# OSO-SCAP-A1-01.net
KiCad netlist of a schematic drawn in EAGLE
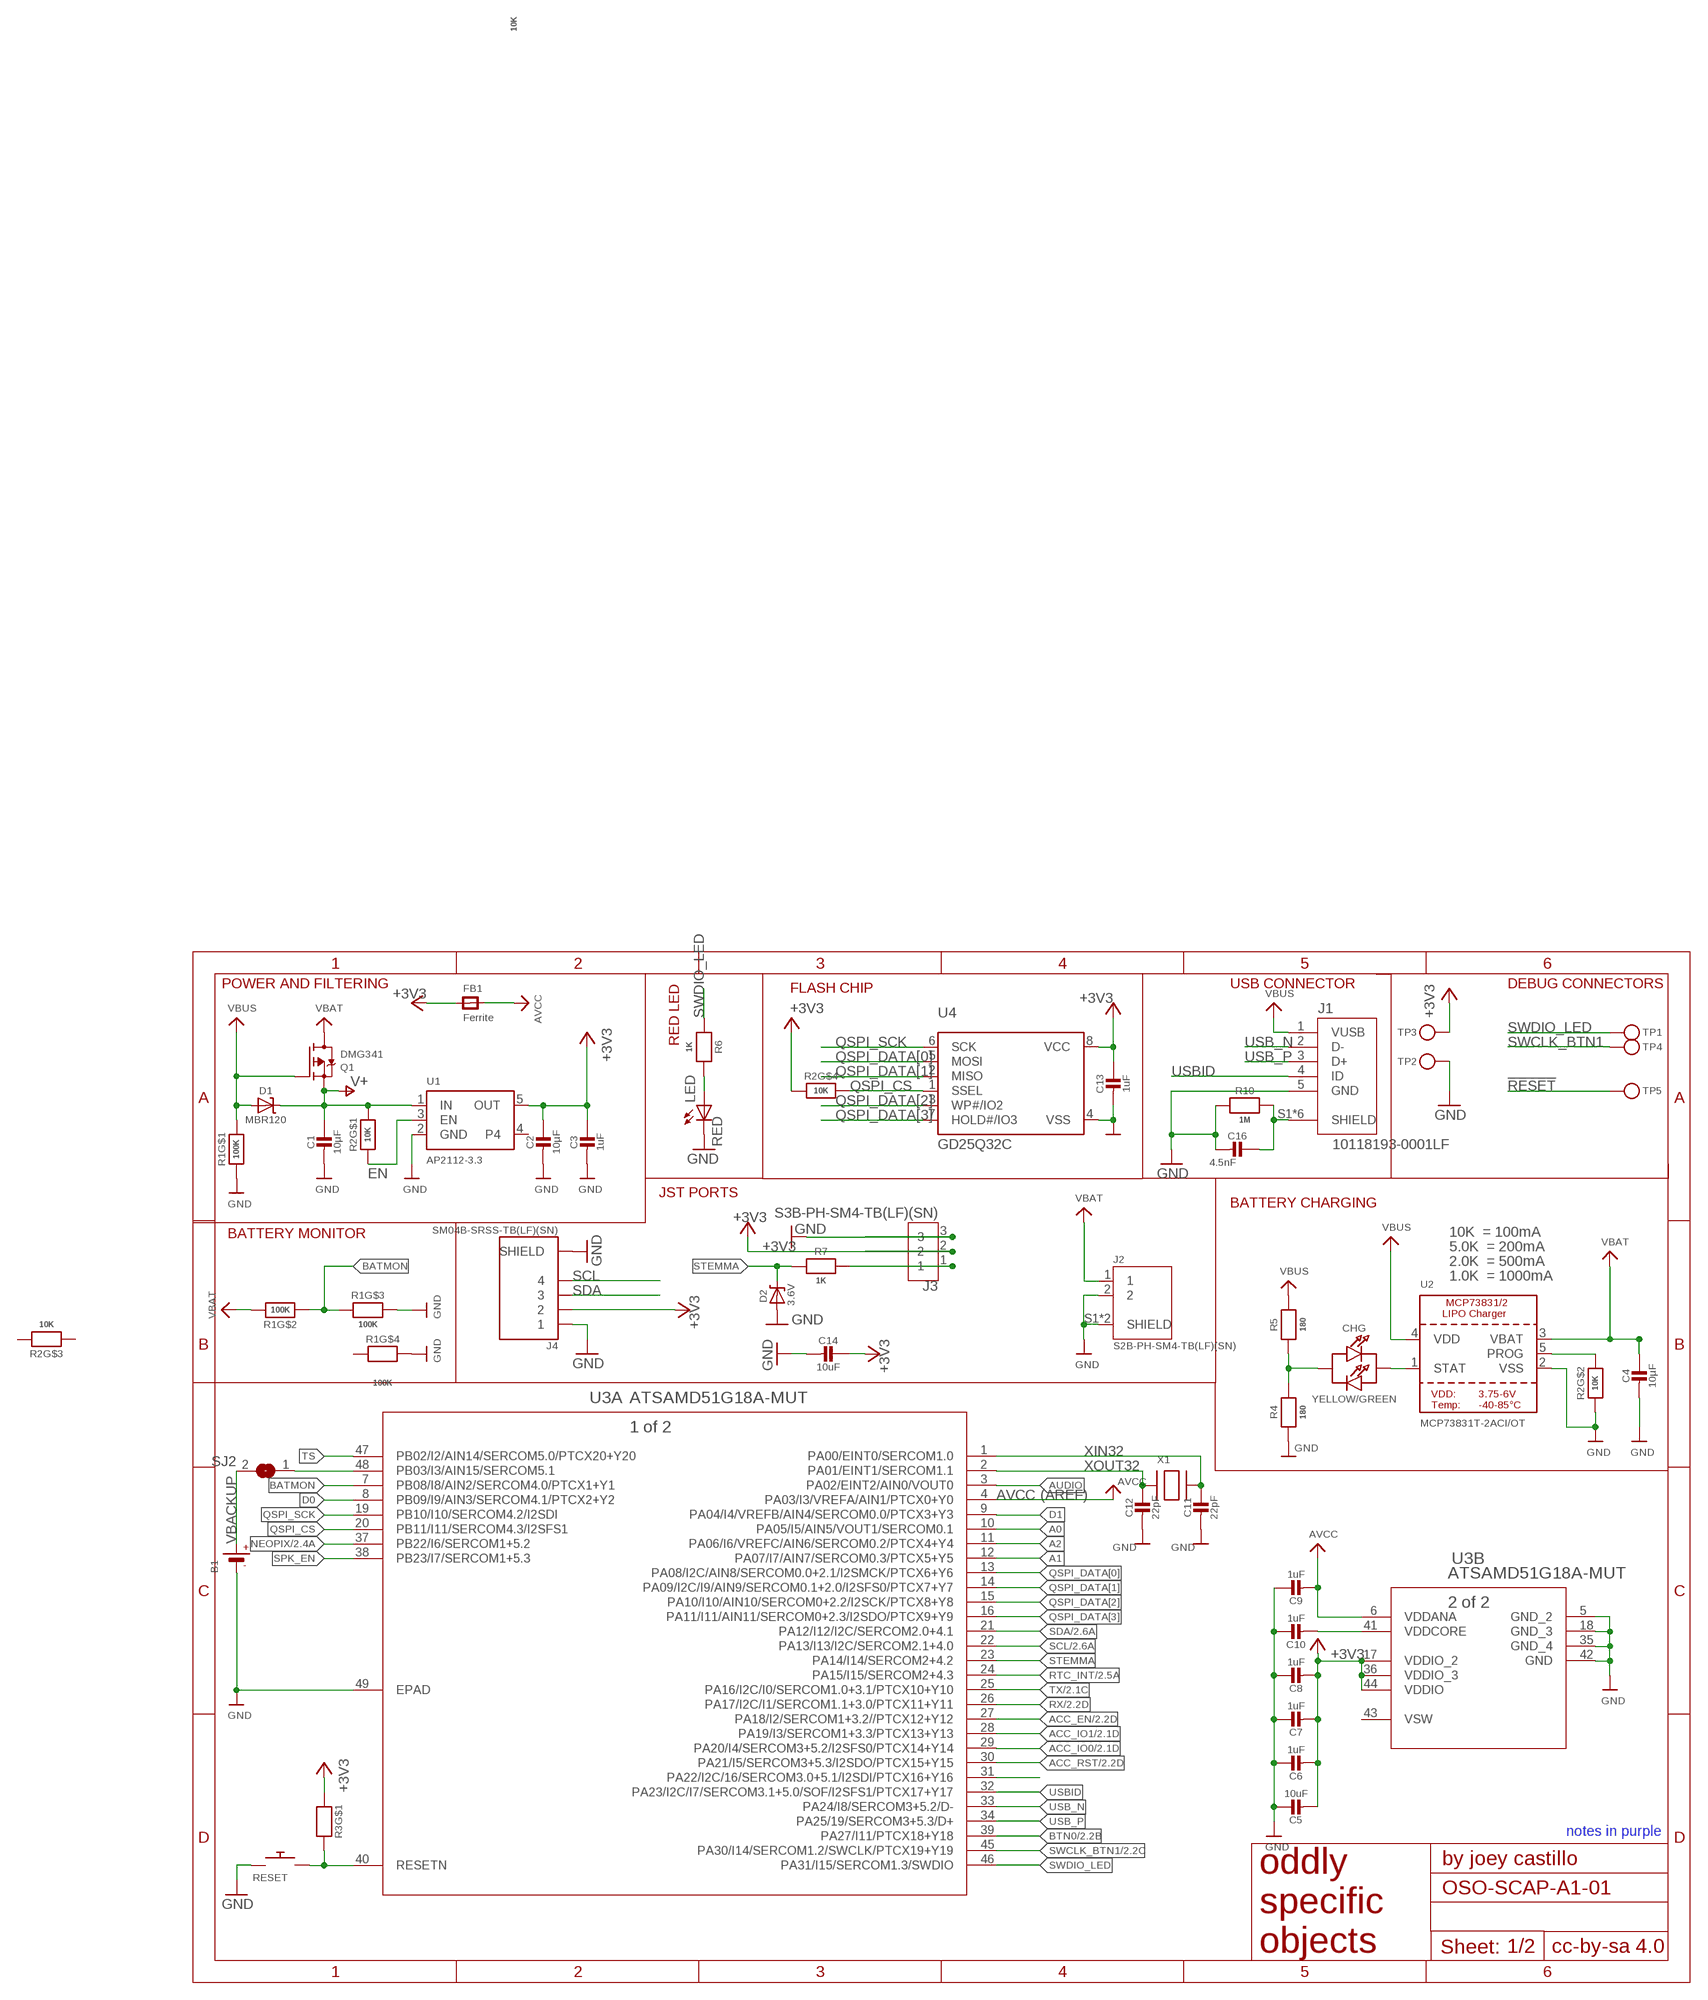
[diagram p0: schematic, sheet 1]
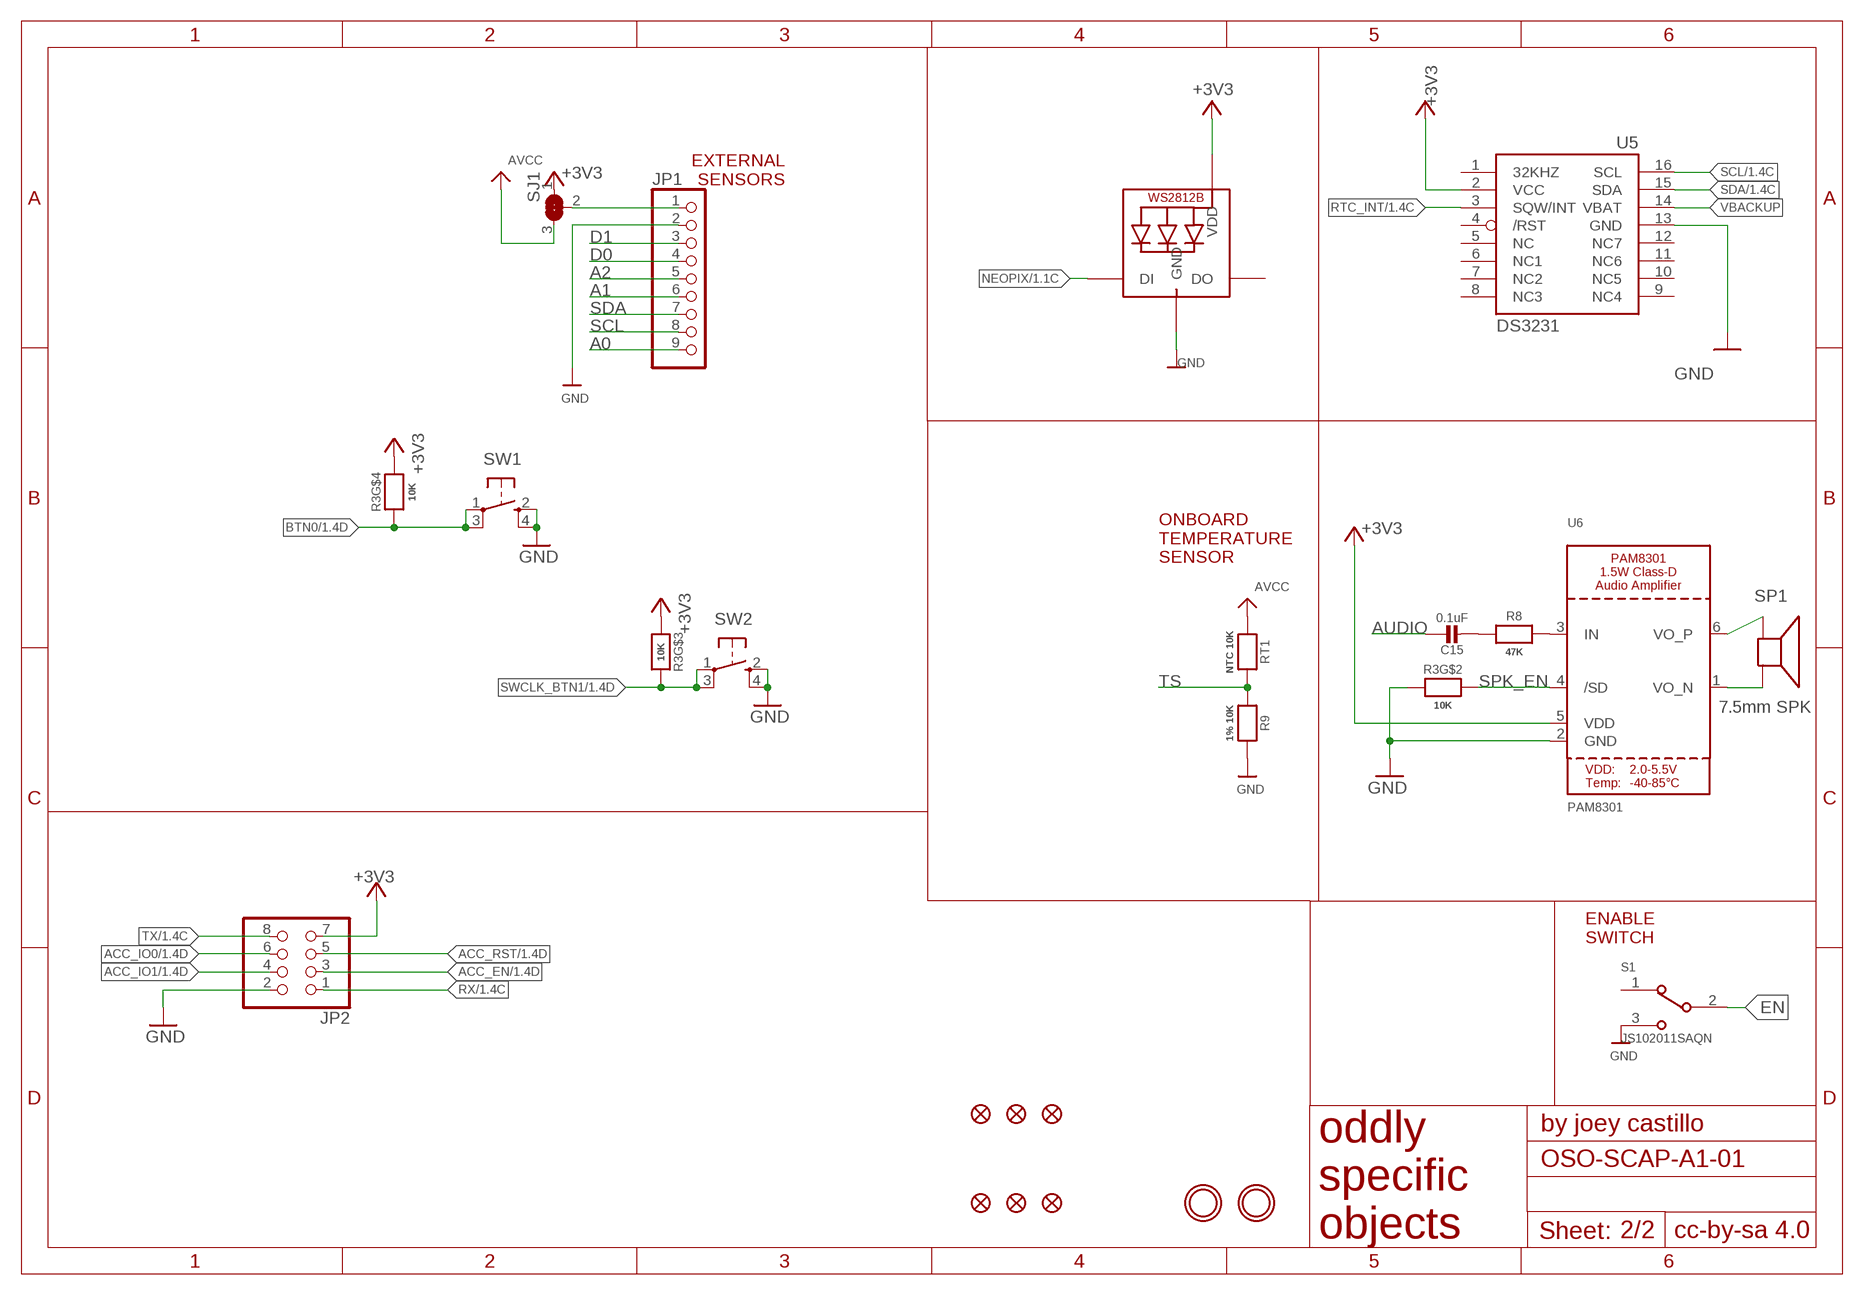
[diagram p1: schematic, sheet 2]

(export (version "E")
  (design (tool "Eeschema 10.0.6"))
  (components
    (comp (ref "C15")
      (value "0.1uF")
      (footprint "eagle-import:0805-NO")
      (libsource (lib "eagle-import") (part "CAP_CERAMIC0805-NOOUTLINE"))
    )
    (comp (ref "FID1")
      (value "FIDUCIAL_1MM")
      (footprint "eagle-import:FIDUCIAL_1MM")
      (libsource (lib "eagle-import") (part "FIDUCIAL_1MM"))
    )
    (comp (ref "FID2")
      (value "FIDUCIAL_1MM")
      (footprint "eagle-import:FIDUCIAL_1MM")
      (libsource (lib "eagle-import") (part "FIDUCIAL_1MM"))
    )
    (comp (ref "FID3")
      (value "FIDUCIAL_1MM")
      (footprint "eagle-import:FIDUCIAL_1MM")
      (libsource (lib "eagle-import") (part "FIDUCIAL_1MM"))
    )
    (comp (ref "FID4")
      (value "FIDUCIAL_1MM")
      (footprint "eagle-import:FIDUCIAL_1MM")
      (libsource (lib "eagle-import") (part "FIDUCIAL_1MM"))
    )
    (comp (ref "FID5")
      (value "FIDUCIAL_1MM")
      (footprint "eagle-import:FIDUCIAL_1MM")
      (libsource (lib "eagle-import") (part "FIDUCIAL_1MM"))
    )
    (comp (ref "FID6")
      (value "FIDUCIAL_1MM")
      (footprint "eagle-import:FIDUCIAL_1MM")
      (libsource (lib "eagle-import") (part "FIDUCIAL_1MM"))
    )
    (comp (ref "JP1")
      (value "HEADER-1X9_JSTSH")
      (footprint "eagle-import:JST_SH9")
      (libsource (lib "eagle-import") (part "HEADER-1X9_JSTSH"))
    )
    (comp (ref "JP2")
      (value "PINHD-2X4SMT")
      (footprint "eagle-import:PINHD_2X4_SMT")
      (libsource (lib "eagle-import") (part "PINHD-2X4SMT"))
    )
    (comp (ref "NEOPIX")
      (value "WS2812B_4020")
      (footprint "eagle-import:WS2812B_4020")
      (libsource (lib "eagle-import") (part "WS2812B_4020"))
    )
    (comp (ref "R3")
      (value "10K")
      (footprint "eagle-import:EXBV8V")
      (fields (field (name "MANUFACTURER_PART_NUMBER") "EXBV8V103JV"))
      (libsource (lib "eagle-import") (part "EXB-V8V103JV-GOOD"))
    )
    (comp (ref "R8")
      (value "47K")
      (footprint "eagle-import:0805-NO")
      (libsource (lib "eagle-import") (part "RESISTOR0805_NOOUTLINE"))
    )
    (comp (ref "R9")
      (value "1% 10K")
      (footprint "eagle-import:0805-NO")
      (libsource (lib "eagle-import") (part "RESISTOR0805_NOOUTLINE"))
    )
    (comp (ref "RT1")
      (value "NTC 10K")
      (footprint "eagle-import:0805-NO")
      (libsource (lib "eagle-import") (part "RESISTOR0805_NOOUTLINE"))
    )
    (comp (ref "S1")
      (value "JS102011SAQN")
      (footprint "eagle-import:SW_JS102011SAQN")
      (fields (field (name "DIGI-KEY_PART_NUMBER") "401-1999-1-ND") (field (name "MF") "C&K"))
      (libsource (lib "eagle-import") (part "JS102011SAQN"))
    )
    (comp (ref "SJ1")
      (value "SOLDERJUMPER_2WAY")
      (footprint "eagle-import:SOLDERJUMPER_2WAY_OPEN_NOPASTE")
      (libsource (lib "eagle-import") (part "SOLDERJUMPER_2WAY"))
    )
    (comp (ref "SP1")
      (value "7.5mm SPK")
      (footprint "eagle-import:BUZZER_SMT_5MM")
      (libsource (lib "eagle-import") (part "SPEAKER_BUZZER5MM"))
    )
    (comp (ref "SW1")
      (value "SPST_TACT-KMR2")
      (footprint "eagle-import:KMR2")
      (libsource (lib "eagle-import") (part "SPST_TACT-KMR2"))
    )
    (comp (ref "SW2")
      (value "SPST_TACT-KMR2")
      (footprint "eagle-import:KMR2")
      (libsource (lib "eagle-import") (part "SPST_TACT-KMR2"))
    )
    (comp (ref "U$1")
      (value "MOUNTINGHOLE2.5")
      (footprint "eagle-import:MOUNTINGHOLE_2.5_PLATED")
      (libsource (lib "eagle-import") (part "MOUNTINGHOLE2.5"))
    )
    (comp (ref "U$4")
      (value "MOUNTINGHOLE2.5")
      (footprint "eagle-import:MOUNTINGHOLE_2.5_PLATED")
      (libsource (lib "eagle-import") (part "MOUNTINGHOLE2.5"))
    )
    (comp (ref "U5")
      (value "DS3231/SO")
      (footprint "eagle-import:SO16W")
      (libsource (lib "eagle-import") (part "DS3231/SO"))
    )
    (comp (ref "U6")
      (value "PAM8301")
      (footprint "eagle-import:SOT23-6")
      (libsource (lib "eagle-import") (part "PAM8301"))
    )
    (comp (ref "B1")
      (value "CR1220")
      (footprint "eagle-import:CR1220-2")
      (libsource (lib "eagle-import") (part "BATTERYCR1220_2"))
    )
    (comp (ref "C1")
      (value "10µF")
      (footprint "eagle-import:0805-NO")
      (libsource (lib "eagle-import") (part "CAP_CERAMIC0805-NOOUTLINE"))
    )
    (comp (ref "C2")
      (value "10µF")
      (footprint "eagle-import:0805-NO")
      (libsource (lib "eagle-import") (part "CAP_CERAMIC0805-NOOUTLINE"))
    )
    (comp (ref "C3")
      (value "1uF")
      (footprint "eagle-import:0805-NO")
      (libsource (lib "eagle-import") (part "CAP_CERAMIC0805-NOOUTLINE"))
    )
    (comp (ref "C4")
      (value "10µF")
      (footprint "eagle-import:0805-NO")
      (libsource (lib "eagle-import") (part "CAP_CERAMIC0805-NOOUTLINE"))
    )
    (comp (ref "C5")
      (value "10uF")
      (footprint "eagle-import:0805_10MGAP")
      (libsource (lib "eagle-import") (part "CAP_CERAMIC0805_10MGAP"))
    )
    (comp (ref "C6")
      (value "1uF")
      (footprint "eagle-import:0805-NO")
      (libsource (lib "eagle-import") (part "CAP_CERAMIC0805-NOOUTLINE"))
    )
    (comp (ref "C7")
      (value "1uF")
      (footprint "eagle-import:0805-NO")
      (libsource (lib "eagle-import") (part "CAP_CERAMIC0805-NOOUTLINE"))
    )
    (comp (ref "C8")
      (value "1uF")
      (footprint "eagle-import:0805-NO")
      (libsource (lib "eagle-import") (part "CAP_CERAMIC0805-NOOUTLINE"))
    )
    (comp (ref "C9")
      (value "1uF")
      (footprint "eagle-import:0805_10MGAP")
      (libsource (lib "eagle-import") (part "CAP_CERAMIC0805_10MGAP"))
    )
    (comp (ref "C10")
      (value "1uF")
      (footprint "eagle-import:0805_10MGAP")
      (libsource (lib "eagle-import") (part "CAP_CERAMIC0805_10MGAP"))
    )
    (comp (ref "C11")
      (value "22pF")
      (footprint "eagle-import:0805-NO")
      (libsource (lib "eagle-import") (part "CAP_CERAMIC0805-NOOUTLINE"))
    )
    (comp (ref "C12")
      (value "22pF")
      (footprint "eagle-import:0805-NO")
      (libsource (lib "eagle-import") (part "CAP_CERAMIC0805-NOOUTLINE"))
    )
    (comp (ref "C13")
      (value "1uF")
      (footprint "eagle-import:0805-NO")
      (libsource (lib "eagle-import") (part "CAP_CERAMIC0805-NOOUTLINE"))
    )
    (comp (ref "C14")
      (value "10uF")
      (footprint "eagle-import:0805-NO")
      (libsource (lib "eagle-import") (part "CAP_CERAMIC0805-NOOUTLINE"))
    )
    (comp (ref "C16")
      (value "4.5nF")
      (footprint "eagle-import:0805-NO")
      (libsource (lib "eagle-import") (part "CAP_CERAMIC0805-NOOUTLINE"))
    )
    (comp (ref "CHG")
      (value "YELLOW/GREEN")
      (footprint "eagle-import:CHIPLED_1206")
      (libsource (lib "eagle-import") (part "LED_BIDI1206"))
    )
    (comp (ref "D1")
      (value "MBR120")
      (footprint "eagle-import:SOD-123")
      (libsource (lib "eagle-import") (part "DIODE-SCHOTTKYSOD-123"))
    )
    (comp (ref "D2")
      (value "3.6V")
      (footprint "eagle-import:SOD-123")
      (libsource (lib "eagle-import") (part "DIODE-ZENERSOD123"))
    )
    (comp (ref "FB1")
      (value "Ferrite")
      (footprint "eagle-import:_0805MP")
      (libsource (lib "eagle-import") (part "FERRITE_0805MP"))
    )
    (comp (ref "J1")
      (value "10118193-0001LF")
      (footprint "eagle-import:FCI_10118193-0001LF")
      (fields (field (name "DIGI-KEY_PART_NUMBER") "609-4616-1-ND") (field (name "MF") "Amphenol ICC"))
      (libsource (lib "eagle-import") (part "10118193-0001LF"))
    )
    (comp (ref "J2")
      (value "S2B-PH-SM4-TB(LF)(SN)")
      (footprint "eagle-import:JST_S2B-PH-SM4-TB(LF)(SN)")
      (fields
        (field (name "DIGI-KEY_PART_NUMBER") "455-1749-1-ND")
        (field (name "MF") "JST Sales")
        (field (name "MP") "S2B-PH-SM4-TB_LF__SN_")
      )
      (libsource (lib "eagle-import") (part "S2B-PH-SM4-TB(LF)(SN)"))
    )
    (comp (ref "J3")
      (value "S3B-PH-SM4-TB(LF)(SN)")
      (footprint "eagle-import:JST_S3B-PH-SM4-TB(LF)(SN)")
      (fields
        (field (name "DIGI-KEY_PART_NUMBER") "455-1750-1-ND")
        (field (name "MF") "JST Sales")
        (field (name "MP") "S3B-PH-SM4-TB_LF__SN_")
      )
      (libsource (lib "eagle-import") (part "S3B-PH-SM4-TB(LF)(SN)"))
    )
    (comp (ref "J4")
      (value "SM04B-SRSS-TB(LF)(SN)")
      (footprint "eagle-import:JST_SM04B-SRSS-TB(LF)(SN)")
      (fields
        (field (name "DIGI-KEY_PART_NUMBER") "455-1804-1-ND")
        (field (name "MF") "JST Sales")
        (field (name "MP") "SM04B-SRSS-TB_LF__SN_")
      )
      (libsource (lib "eagle-import") (part "SM04B-SRSS-TB(LF)(SN)"))
    )
    (comp (ref "LED")
      (value "RED")
      (footprint "eagle-import:CHIPLED_1206")
      (libsource (lib "eagle-import") (part "LEDCHIPLED_1206"))
    )
    (comp (ref "Q1")
      (value "DMG341")
      (footprint "eagle-import:SOT23-R")
      (libsource (lib "eagle-import") (part "MOSFET-P"))
    )
    (comp (ref "R1")
      (value "100K")
      (footprint "eagle-import:EXBV8V")
      (fields (field (name "MANUFACTURER_PART_NUMBER") "EXBV8V103JV"))
      (libsource (lib "eagle-import") (part "EXB-V8V103JV-GOOD"))
    )
    (comp (ref "R2")
      (value "10K")
      (footprint "eagle-import:EXBV8V")
      (fields (field (name "MANUFACTURER_PART_NUMBER") "EXBV8V103JV"))
      (libsource (lib "eagle-import") (part "EXB-V8V103JV-GOOD"))
    )
    (comp (ref "R4")
      (value "180")
      (footprint "eagle-import:0805-NO")
      (libsource (lib "eagle-import") (part "RESISTOR0805_NOOUTLINE"))
    )
    (comp (ref "R5")
      (value "180")
      (footprint "eagle-import:0805-NO")
      (libsource (lib "eagle-import") (part "RESISTOR0805_NOOUTLINE"))
    )
    (comp (ref "R6")
      (value "1K")
      (footprint "eagle-import:0805-NO")
      (libsource (lib "eagle-import") (part "RESISTOR0805_NOOUTLINE"))
    )
    (comp (ref "R7")
      (value "1K")
      (footprint "eagle-import:0805-NO")
      (libsource (lib "eagle-import") (part "RESISTOR0805_NOOUTLINE"))
    )
    (comp (ref "R10")
      (value "1M")
      (footprint "eagle-import:0805-NO")
      (libsource (lib "eagle-import") (part "RESISTOR0805_NOOUTLINE"))
    )
    (comp (ref "RESET")
      (value "SWITCH_PUSHBUTTONC&K_KSS")
      (footprint "eagle-import:BTN_CK_KSS")
      (libsource (lib "eagle-import") (part "SWITCH_PUSHBUTTONC&K_KSS"))
    )
    (comp (ref "SJ2")
      (value "SOLDERJUMPERREFLOW_NOPASTE")
      (footprint "eagle-import:SOLDERJUMPER_REFLOW_NOPASTE")
      (libsource (lib "eagle-import") (part "SOLDERJUMPERREFLOW_NOPASTE"))
    )
    (comp (ref "TP1")
      (value "TESTPOINTROUND1.5MMNO")
      (footprint "eagle-import:TESTPOINT_ROUND_1.5MM_NO")
      (libsource (lib "eagle-import") (part "TESTPOINTROUND1.5MMNO"))
    )
    (comp (ref "TP2")
      (value "TESTPOINTROUND1.5MMNO")
      (footprint "eagle-import:TESTPOINT_ROUND_1.5MM_NO")
      (libsource (lib "eagle-import") (part "TESTPOINTROUND1.5MMNO"))
    )
    (comp (ref "TP3")
      (value "TESTPOINTROUND1.5MMNO")
      (footprint "eagle-import:TESTPOINT_ROUND_1.5MM_NO")
      (libsource (lib "eagle-import") (part "TESTPOINTROUND1.5MMNO"))
    )
    (comp (ref "TP4")
      (value "TESTPOINTROUND1.5MMNO")
      (footprint "eagle-import:TESTPOINT_ROUND_1.5MM_NO")
      (libsource (lib "eagle-import") (part "TESTPOINTROUND1.5MMNO"))
    )
    (comp (ref "TP5")
      (value "TESTPOINTROUND1.5MMNO")
      (footprint "eagle-import:TESTPOINT_ROUND_1.5MM_NO")
      (libsource (lib "eagle-import") (part "TESTPOINTROUND1.5MMNO"))
    )
    (comp (ref "U1")
      (value "AP2112-3.3")
      (footprint "eagle-import:SOT23-5")
      (libsource (lib "eagle-import") (part "VREG_SOT23-5"))
    )
    (comp (ref "U2")
      (value "MCP73831T-2ACI/OT")
      (footprint "eagle-import:SOT23-5")
      (libsource (lib "eagle-import") (part "MCP73831/2"))
    )
    (comp (ref "U3")
      (value "ATSAMD51G18A-MUT")
      (footprint "eagle-import:QFN48_7X7MC")
      (fields (field (name "COPYRIGHT") "Copyright (C) 2018 Accelerated Designs. All rights reserved"))
      (libsource (lib "eagle-import") (part "ATSAMD51G18A-MUT"))
    )
    (comp (ref "U4")
      (value "GD25Q32C")
      (footprint "eagle-import:MICROBUILDER_SOIC8_150MIL")
      (libsource (lib "eagle-import") (part "MICROBUILDER_SPIFLASH_SOIC8"))
    )
    (comp (ref "X1")
      (value "XTAL-3.2X1.5")
      (footprint "eagle-import:XTAL3215")
      (libsource (lib "eagle-import") (part "XTAL-3.2X1.5"))
    )
  )
  (nets
    (net (code "1") (name "+3V3") (class "Default")
      (node (ref "C13") (pin "1") (pinfunction "1_1") (pintype "passive"))
      (node (ref "C14") (pin "1") (pinfunction "1_1") (pintype "passive"))
      (node (ref "C2") (pin "1") (pinfunction "1_1") (pintype "passive"))
      (node (ref "C3") (pin "1") (pinfunction "1_1") (pintype "passive"))
      (node (ref "C5") (pin "2") (pinfunction "2_2") (pintype "passive"))
      (node (ref "C6") (pin "2") (pinfunction "2_2") (pintype "passive"))
      (node (ref "C7") (pin "2") (pinfunction "2_2") (pintype "passive"))
      (node (ref "C8") (pin "2") (pinfunction "2_2") (pintype "passive"))
      (node (ref "FB1") (pin "1") (pinfunction "P$1_1") (pintype "passive"))
      (node (ref "J3") (pin "2") (pinfunction "2_2") (pintype "passive"))
      (node (ref "J4") (pin "2") (pinfunction "2_2") (pintype "passive"))
      (node (ref "JP2") (pin "7") (pinfunction "7_7") (pintype "passive"))
      (node (ref "NEOPIX") (pin "2") (pinfunction "VDD_2") (pintype "power_in"))
      (node (ref "R2") (pin "4") (pinfunction "1_4") (pintype "passive"))
      (node (ref "R3") (pin "1") (pinfunction "1_1") (pintype "passive"))
      (node (ref "R3") (pin "3") (pinfunction "1_3") (pintype "passive"))
      (node (ref "R3") (pin "5") (pinfunction "2_5") (pintype "passive"))
      (node (ref "SJ1") (pin "1") (pinfunction "1_1") (pintype "passive"))
      (node (ref "TP3") (pin "P$1") (pinfunction "P$1_P$1") (pintype "bidirectional"))
      (node (ref "U1") (pin "5") (pinfunction "OUT_5") (pintype "power_in"))
      (node (ref "U3") (pin "17") (pinfunction "VDDIO_2_17") (pintype "power_in"))
      (node (ref "U3") (pin "36") (pinfunction "VDDIO_3_36") (pintype "power_in"))
      (node (ref "U3") (pin "44") (pinfunction "VDDIO_44") (pintype "power_in"))
      (node (ref "U4") (pin "8") (pinfunction "VCC_8") (pintype "bidirectional"))
      (node (ref "U5") (pin "2") (pinfunction "VCC_2") (pintype "power_in"))
      (node (ref "U6") (pin "5") (pinfunction "VDD_5") (pintype "power_in"))
    )
    (net (code "2") (name "A0") (class "Default")
      (node (ref "JP1") (pin "9") (pinfunction "9_9") (pintype "passive"))
      (node (ref "U3") (pin "10") (pinfunction "PA05/I5/AIN5/VOUT1/SERCOM0.1_10") (pintype "bidirectional"))
    )
    (net (code "3") (name "A1") (class "Default")
      (node (ref "JP1") (pin "6") (pinfunction "6_6") (pintype "passive"))
      (node (ref "U3") (pin "12") (pinfunction "PA07/I7/AIN7/SERCOM0.3/PTCX5+Y5_12") (pintype "bidirectional"))
    )
    (net (code "4") (name "A2") (class "Default")
      (node (ref "JP1") (pin "5") (pinfunction "5_5") (pintype "passive"))
      (node (ref "U3") (pin "11") (pinfunction "PA06/I6/VREFC/AIN6/SERCOM0.2/PTCX4+Y4_11") (pintype "bidirectional"))
    )
    (net (code "5") (name "ACC_EN") (class "Default")
      (node (ref "JP2") (pin "3") (pinfunction "3_3") (pintype "passive"))
      (node (ref "U3") (pin "27") (pinfunction "PA18/I2/SERCOM1+3.2//PTCX12+Y12_27") (pintype "bidirectional"))
    )
    (net (code "6") (name "ACC_IO0") (class "Default")
      (node (ref "JP2") (pin "6") (pinfunction "6_6") (pintype "passive"))
      (node (ref "U3") (pin "29") (pinfunction "PA20/I4/SERCOM3+5.2/I2SFS0/PTCX14+Y14_29") (pintype "bidirectional"))
    )
    (net (code "7") (name "ACC_IO1") (class "Default")
      (node (ref "JP2") (pin "4") (pinfunction "4_4") (pintype "passive"))
      (node (ref "U3") (pin "28") (pinfunction "PA19/I3/SERCOM1+3.3/PTCX13+Y13_28") (pintype "bidirectional"))
    )
    (net (code "8") (name "ACC_RST") (class "Default")
      (node (ref "JP2") (pin "5") (pinfunction "5_5") (pintype "passive"))
      (node (ref "U3") (pin "30") (pinfunction "PA21/I5/SERCOM3+5.3/I2SDO/PTCX15+Y15_30") (pintype "bidirectional"))
    )
    (net (code "9") (name "AUDIO") (class "Default")
      (node (ref "C15") (pin "1") (pinfunction "1_1") (pintype "passive"))
      (node (ref "U3") (pin "3") (pinfunction "PA02/EINT2/AIN0/VOUT0_3") (pintype "bidirectional"))
    )
    (net (code "10") (name "AVCC") (class "Default")
      (node (ref "C9") (pin "2") (pinfunction "2_2") (pintype "passive"))
      (node (ref "FB1") (pin "2") (pinfunction "P$2_2") (pintype "passive"))
      (node (ref "RT1") (pin "1") (pinfunction "1_1") (pintype "passive"))
      (node (ref "SJ1") (pin "3") (pinfunction "3_3") (pintype "passive"))
      (node (ref "U3") (pin "4") (pinfunction "PA03/I3/VREFA/AIN1/PTCX0+Y0_4") (pintype "bidirectional"))
      (node (ref "U3") (pin "6") (pinfunction "VDDANA_6") (pintype "power_in"))
    )
    (net (code "11") (name "BATMON") (class "Default")
      (node (ref "R1") (pin "2") (pinfunction "1_2") (pintype "passive"))
      (node (ref "R1") (pin "3") (pinfunction "1_3") (pintype "passive"))
      (node (ref "U3") (pin "7") (pinfunction "PB08/I8/AIN2/SERCOM4.0/PTCX1+Y1_7") (pintype "bidirectional"))
    )
    (net (code "12") (name "BTN0") (class "Default")
      (node (ref "R3") (pin "4") (pinfunction "1_4") (pintype "passive"))
      (node (ref "SW1") (pin "1") (pinfunction "P_1") (pintype "passive"))
      (node (ref "SW1") (pin "3") (pinfunction "P1_3") (pintype "passive"))
      (node (ref "U3") (pin "39") (pinfunction "PA27/I11/PTCX18+Y18_39") (pintype "bidirectional"))
    )
    (net (code "13") (name "D0") (class "Default")
      (node (ref "JP1") (pin "4") (pinfunction "4_4") (pintype "passive"))
      (node (ref "U3") (pin "8") (pinfunction "PB09/I9/AIN3/SERCOM4.1/PTCX2+Y2_8") (pintype "bidirectional"))
    )
    (net (code "14") (name "D1") (class "Default")
      (node (ref "JP1") (pin "3") (pinfunction "3_3") (pintype "passive"))
      (node (ref "U3") (pin "9") (pinfunction "PA04/I4/VREFB/AIN4/SERCOM0.0/PTCX3+Y3_9") (pintype "bidirectional"))
    )
    (net (code "15") (name "EN") (class "Default")
      (node (ref "R2") (pin "1") (pinfunction "1_1") (pintype "passive"))
      (node (ref "S1") (pin "2") (pinfunction "2_2") (pintype "passive"))
      (node (ref "U1") (pin "3") (pinfunction "EN_3") (pintype "input"))
    )
    (net (code "16") (name "GND") (class "Default")
      (node (ref "B1") (pin "-") (pinfunction "-_-") (pintype "passive"))
      (node (ref "C1") (pin "2") (pinfunction "2_2") (pintype "passive"))
      (node (ref "C10") (pin "1") (pinfunction "1_1") (pintype "passive"))
      (node (ref "C11") (pin "2") (pinfunction "2_2") (pintype "passive"))
      (node (ref "C12") (pin "2") (pinfunction "2_2") (pintype "passive"))
      (node (ref "C13") (pin "2") (pinfunction "2_2") (pintype "passive"))
      (node (ref "C14") (pin "2") (pinfunction "2_2") (pintype "passive"))
      (node (ref "C16") (pin "2") (pinfunction "2_2") (pintype "passive"))
      (node (ref "C2") (pin "2") (pinfunction "2_2") (pintype "passive"))
      (node (ref "C3") (pin "2") (pinfunction "2_2") (pintype "passive"))
      (node (ref "C4") (pin "2") (pinfunction "2_2") (pintype "passive"))
      (node (ref "C5") (pin "1") (pinfunction "1_1") (pintype "passive"))
      (node (ref "C6") (pin "1") (pinfunction "1_1") (pintype "passive"))
      (node (ref "C7") (pin "1") (pinfunction "1_1") (pintype "passive"))
      (node (ref "C8") (pin "1") (pinfunction "1_1") (pintype "passive"))
      (node (ref "C9") (pin "1") (pinfunction "1_1") (pintype "passive"))
      (node (ref "D2") (pin "A") (pinfunction "A_A") (pintype "passive"))
      (node (ref "J1") (pin "5") (pinfunction "GND_5") (pintype "passive"))
      (node (ref "J2") (pin "2") (pinfunction "2_2") (pintype "passive"))
      (node (ref "J2") (pin "S1") (pinfunction "SHIELD_S1") (pintype "passive"))
      (node (ref "J2") (pin "S2") (pinfunction "SHIELD_S2") (pintype "passive"))
      (node (ref "J3") (pin "3") (pinfunction "3_3") (pintype "passive"))
      (node (ref "J4") (pin "1") (pinfunction "1_1") (pintype "passive"))
      (node (ref "J4") (pin "S1") (pinfunction "SHIELD_S1") (pintype "passive"))
      (node (ref "J4") (pin "S2") (pinfunction "SHIELD_S2") (pintype "passive"))
      (node (ref "JP1") (pin "2") (pinfunction "2_2") (pintype "passive"))
      (node (ref "JP2") (pin "2") (pinfunction "2_2") (pintype "passive"))
      (node (ref "LED") (pin "C") (pinfunction "C_C") (pintype "passive"))
      (node (ref "NEOPIX") (pin "4") (pinfunction "GND_4") (pintype "power_in"))
      (node (ref "R1") (pin "1") (pinfunction "1_1") (pintype "passive"))
      (node (ref "R1") (pin "5") (pinfunction "2_5") (pintype "passive"))
      (node (ref "R1") (pin "6") (pinfunction "2_6") (pintype "passive"))
      (node (ref "R10") (pin "2") (pinfunction "2_2") (pintype "passive"))
      (node (ref "R2") (pin "2") (pinfunction "1_2") (pintype "passive"))
      (node (ref "R3") (pin "2") (pinfunction "1_2") (pintype "passive"))
      (node (ref "R4") (pin "1") (pinfunction "1_1") (pintype "passive"))
      (node (ref "R9") (pin "2") (pinfunction "2_2") (pintype "passive"))
      (node (ref "RESET") (pin "P$1") (pinfunction "P$1_P$1") (pintype "passive"))
      (node (ref "S1") (pin "3") (pinfunction "3_3") (pintype "passive"))
      (node (ref "SW1") (pin "2") (pinfunction "S_2") (pintype "passive"))
      (node (ref "SW1") (pin "4") (pinfunction "S1_4") (pintype "passive"))
      (node (ref "SW2") (pin "2") (pinfunction "S_2") (pintype "passive"))
      (node (ref "SW2") (pin "4") (pinfunction "S1_4") (pintype "passive"))
      (node (ref "TP2") (pin "P$1") (pinfunction "P$1_P$1") (pintype "bidirectional"))
      (node (ref "U1") (pin "2") (pinfunction "GND_2") (pintype "power_in"))
      (node (ref "U2") (pin "2") (pinfunction "VSS_2") (pintype "power_in"))
      (node (ref "U3") (pin "18") (pinfunction "GND_3_18") (pintype "passive"))
      (node (ref "U3") (pin "35") (pinfunction "GND_4_35") (pintype "passive"))
      (node (ref "U3") (pin "42") (pinfunction "GND_42") (pintype "passive"))
      (node (ref "U3") (pin "49") (pinfunction "EPAD_49") (pintype "passive"))
      (node (ref "U3") (pin "5") (pinfunction "GND_2_5") (pintype "passive"))
      (node (ref "U4") (pin "4") (pinfunction "VSS_4") (pintype "bidirectional"))
      (node (ref "U5") (pin "13") (pinfunction "GND_13") (pintype "power_in"))
      (node (ref "U6") (pin "2") (pinfunction "GND_2") (pintype "power_in"))
    )
    (net (code "17") (name "NEOPIX") (class "Default")
      (node (ref "NEOPIX") (pin "1") (pinfunction "DI_1") (pintype "input"))
      (node (ref "U3") (pin "37") (pinfunction "PB22/I6/SERCOM1+5.2_37") (pintype "bidirectional"))
    )
    (net (code "18") (name "Net-(C15-Pad2)") (class "Default")
      (node (ref "C15") (pin "2") (pinfunction "2_2") (pintype "passive"))
      (node (ref "R8") (pin "1") (pinfunction "1_1") (pintype "passive"))
    )
    (net (code "19") (name "Net-(C16-Pad1)") (class "Default")
      (node (ref "C16") (pin "1") (pinfunction "1_1") (pintype "passive"))
      (node (ref "J1") (pin "S1") (pinfunction "SHIELD_S1") (pintype "passive"))
      (node (ref "J1") (pin "S2") (pinfunction "SHIELD_S2") (pintype "passive"))
      (node (ref "J1") (pin "S3") (pinfunction "SHIELD_S3") (pintype "passive"))
      (node (ref "J1") (pin "S4") (pinfunction "SHIELD_S4") (pintype "passive"))
      (node (ref "J1") (pin "S5") (pinfunction "SHIELD_S5") (pintype "passive"))
      (node (ref "J1") (pin "S6") (pinfunction "SHIELD_S6") (pintype "passive"))
      (node (ref "R10") (pin "1") (pinfunction "1_1") (pintype "passive"))
    )
    (net (code "20") (name "Net-(CHG-PadA)") (class "Default")
      (node (ref "CHG") (pin "A") (pinfunction "A_A") (pintype "passive"))
      (node (ref "R4") (pin "2") (pinfunction "2_2") (pintype "passive"))
      (node (ref "R5") (pin "1") (pinfunction "1_1") (pintype "passive"))
    )
    (net (code "21") (name "Net-(J3-Pad1)") (class "Default")
      (node (ref "J3") (pin "1") (pinfunction "1_1") (pintype "passive"))
      (node (ref "R7") (pin "1") (pinfunction "1_1") (pintype "passive"))
    )
    (net (code "22") (name "Net-(JP1-Pad1)") (class "Default")
      (node (ref "JP1") (pin "1") (pinfunction "1_1") (pintype "passive"))
      (node (ref "SJ1") (pin "2") (pinfunction "2_2") (pintype "passive"))
    )
    (net (code "23") (name "Net-(LED-PadA)") (class "Default")
      (node (ref "LED") (pin "A") (pinfunction "A_A") (pintype "passive"))
      (node (ref "R6") (pin "2") (pinfunction "2_2") (pintype "passive"))
    )
    (net (code "24") (name "Net-(R2B-2)") (class "Default")
      (node (ref "R2") (pin "7") (pinfunction "2_7") (pintype "passive"))
      (node (ref "U2") (pin "5") (pinfunction "PROG_5") (pintype "input"))
    )
    (net (code "25") (name "Net-(U2-STAT)") (class "Default")
      (node (ref "CHG") (pin "C") (pinfunction "C_C") (pintype "passive"))
      (node (ref "U2") (pin "1") (pinfunction "STAT_1") (pintype "output"))
    )
    (net (code "26") (name "Net-(U3A-PB03{slash}I3{slash}AIN15{slash}SERCOM5.1)") (class "Default")
      (node (ref "SJ2") (pin "1") (pinfunction "1_1") (pintype "passive"))
      (node (ref "U3") (pin "48") (pinfunction "PB03/I3/AIN15/SERCOM5.1_48") (pintype "bidirectional"))
    )
    (net (code "27") (name "Net-(U3B-VDDCORE)") (class "Default")
      (node (ref "C10") (pin "2") (pinfunction "2_2") (pintype "passive"))
      (node (ref "U3") (pin "41") (pinfunction "VDDCORE_41") (pintype "bidirectional"))
    )
    (net (code "28") (name "Net-(U6-IN)") (class "Default")
      (node (ref "R8") (pin "2") (pinfunction "2_2") (pintype "passive"))
      (node (ref "U6") (pin "3") (pinfunction "IN_3") (pintype "input"))
    )
    (net (code "29") (name "Net-(U6-VO_N)") (class "Default")
      (node (ref "SP1") (pin "+") (pinfunction "+_+") (pintype "passive"))
      (node (ref "U6") (pin "1") (pinfunction "VO_N_1") (pintype "output"))
    )
    (net (code "30") (name "Net-(U6-VO_P)") (class "Default")
      (node (ref "SP1") (pin "-") (pinfunction "-_-") (pintype "passive"))
      (node (ref "U6") (pin "6") (pinfunction "VO_P_6") (pintype "output"))
    )
    (net (code "31") (name "QSPI_CS") (class "Default")
      (node (ref "R2") (pin "5") (pinfunction "2_5") (pintype "passive"))
      (node (ref "U3") (pin "20") (pinfunction "PB11/I11/SERCOM4.3/I2SFS1_20") (pintype "bidirectional"))
      (node (ref "U4") (pin "1") (pinfunction "SSEL_1") (pintype "bidirectional"))
    )
    (net (code "32") (name "QSPI_DATA[0]") (class "Default")
      (node (ref "U3") (pin "13") (pinfunction "PA08/I2C/AIN8/SERCOM0.0+2.1/I2SMCK/PTCX6+Y6_13") (pintype "bidirectional"))
      (node (ref "U4") (pin "5") (pinfunction "MOSI_5") (pintype "bidirectional"))
    )
    (net (code "33") (name "QSPI_DATA[1]") (class "Default")
      (node (ref "U3") (pin "14") (pinfunction "PA09/I2C/I9/AIN9/SERCOM0.1+2.0/I2SFS0/PTCX7+Y7_14") (pintype "bidirectional"))
      (node (ref "U4") (pin "2") (pinfunction "MISO_2") (pintype "bidirectional"))
    )
    (net (code "34") (name "QSPI_DATA[2]") (class "Default")
      (node (ref "U3") (pin "15") (pinfunction "PA10/I10/AIN10/SERCOM0+2.2/I2SCK/PTCX8+Y8_15") (pintype "bidirectional"))
      (node (ref "U4") (pin "3") (pinfunction "WP#/IO2_3") (pintype "bidirectional"))
    )
    (net (code "35") (name "QSPI_DATA[3]") (class "Default")
      (node (ref "U3") (pin "16") (pinfunction "PA11/I11/AIN11/SERCOM0+2.3/I2SDO/PTCX9+Y9_16") (pintype "bidirectional"))
      (node (ref "U4") (pin "7") (pinfunction "HOLD#/IO3_7") (pintype "bidirectional"))
    )
    (net (code "36") (name "QSPI_SCK") (class "Default")
      (node (ref "U3") (pin "19") (pinfunction "PB10/I10/SERCOM4.2/I2SDI_19") (pintype "bidirectional"))
      (node (ref "U4") (pin "6") (pinfunction "SCK_6") (pintype "bidirectional"))
    )
    (net (code "37") (name "RTC_INT") (class "Default")
      (node (ref "U3") (pin "24") (pinfunction "PA15/I15/SERCOM2+4.3_24") (pintype "bidirectional"))
      (node (ref "U5") (pin "3") (pinfunction "SQW/INT_3") (pintype "output"))
    )
    (net (code "38") (name "RX") (class "Default")
      (node (ref "JP2") (pin "1") (pinfunction "1_1") (pintype "passive"))
      (node (ref "U3") (pin "26") (pinfunction "PA17/I2C/I1/SERCOM1.1+3.0/PTCX11+Y11_26") (pintype "bidirectional"))
    )
    (net (code "39") (name "SCL") (class "Default")
      (node (ref "J4") (pin "4") (pinfunction "4_4") (pintype "passive"))
      (node (ref "JP1") (pin "8") (pinfunction "8_8") (pintype "passive"))
      (node (ref "U3") (pin "22") (pinfunction "PA13/I13/I2C/SERCOM2.1+4.0_22") (pintype "bidirectional"))
      (node (ref "U5") (pin "16") (pinfunction "SCL_16") (pintype "bidirectional"))
    )
    (net (code "40") (name "SDA") (class "Default")
      (node (ref "J4") (pin "3") (pinfunction "3_3") (pintype "passive"))
      (node (ref "JP1") (pin "7") (pinfunction "7_7") (pintype "passive"))
      (node (ref "U3") (pin "21") (pinfunction "PA12/I12/I2C/SERCOM2.0+4.1_21") (pintype "bidirectional"))
      (node (ref "U5") (pin "15") (pinfunction "SDA_15") (pintype "bidirectional"))
    )
    (net (code "41") (name "SPK_EN") (class "Default")
      (node (ref "R3") (pin "7") (pinfunction "2_7") (pintype "passive"))
      (node (ref "U3") (pin "38") (pinfunction "PB23/I7/SERCOM1+5.3_38") (pintype "bidirectional"))
      (node (ref "U6") (pin "4") (pinfunction "/SD_4") (pintype "input"))
    )
    (net (code "42") (name "STEMMA") (class "Default")
      (node (ref "D2") (pin "C") (pinfunction "C_C") (pintype "passive"))
      (node (ref "R7") (pin "2") (pinfunction "2_2") (pintype "passive"))
      (node (ref "U3") (pin "23") (pinfunction "PA14/I14/SERCOM2+4.2_23") (pintype "bidirectional"))
    )
    (net (code "43") (name "SWCLK_BTN1") (class "Default")
      (node (ref "R3") (pin "6") (pinfunction "2_6") (pintype "passive"))
      (node (ref "SW2") (pin "1") (pinfunction "P_1") (pintype "passive"))
      (node (ref "SW2") (pin "3") (pinfunction "P1_3") (pintype "passive"))
      (node (ref "TP4") (pin "P$1") (pinfunction "P$1_P$1") (pintype "bidirectional"))
      (node (ref "U3") (pin "45") (pinfunction "PA30/I14/SERCOM1.2/SWCLK/PTCX19+Y19_45") (pintype "bidirectional"))
    )
    (net (code "44") (name "SWDIO_LED") (class "Default")
      (node (ref "R6") (pin "1") (pinfunction "1_1") (pintype "passive"))
      (node (ref "TP1") (pin "P$1") (pinfunction "P$1_P$1") (pintype "bidirectional"))
      (node (ref "U3") (pin "46") (pinfunction "PA31/I15/SERCOM1.3/SWDIO_46") (pintype "bidirectional"))
    )
    (net (code "45") (name "TS") (class "Default")
      (node (ref "R9") (pin "1") (pinfunction "1_1") (pintype "passive"))
      (node (ref "RT1") (pin "2") (pinfunction "2_2") (pintype "passive"))
      (node (ref "U3") (pin "47") (pinfunction "PB02/I2/AIN14/SERCOM5.0/PTCX20+Y20_47") (pintype "bidirectional"))
    )
    (net (code "46") (name "TX") (class "Default")
      (node (ref "JP2") (pin "8") (pinfunction "8_8") (pintype "passive"))
      (node (ref "U3") (pin "25") (pinfunction "PA16/I2C/I0/SERCOM1.0+3.1/PTCX10+Y10_25") (pintype "bidirectional"))
    )
    (net (code "47") (name "USBID") (class "Default")
      (node (ref "J1") (pin "4") (pinfunction "ID_4") (pintype "passive"))
      (node (ref "U3") (pin "32") (pinfunction "PA23/I2C/I7/SERCOM3.1+5.0/SOF/I2SFS1/PTCX17+Y17_32") (pintype "bidirectional"))
    )
    (net (code "48") (name "USB_N") (class "Default")
      (node (ref "J1") (pin "2") (pinfunction "D-_2") (pintype "passive"))
      (node (ref "U3") (pin "33") (pinfunction "PA24/I8/SERCOM3+5.2/D-_33") (pintype "bidirectional"))
    )
    (net (code "49") (name "USB_P") (class "Default")
      (node (ref "J1") (pin "3") (pinfunction "D+_3") (pintype "passive"))
      (node (ref "U3") (pin "34") (pinfunction "PA25/19/SERCOM3+5.3/D+_34") (pintype "bidirectional"))
    )
    (net (code "50") (name "V+") (class "Default")
      (node (ref "C1") (pin "1") (pinfunction "1_1") (pintype "passive"))
      (node (ref "D1") (pin "C") (pinfunction "C_C") (pintype "passive"))
      (node (ref "Q1") (pin "2") (pinfunction "S_2") (pintype "passive"))
      (node (ref "R2") (pin "8") (pinfunction "2_8") (pintype "passive"))
      (node (ref "U1") (pin "1") (pinfunction "IN_1") (pintype "power_in"))
    )
    (net (code "51") (name "VBACKUP") (class "Default")
      (node (ref "B1") (pin "+") (pinfunction "+_+") (pintype "passive"))
      (node (ref "SJ2") (pin "2") (pinfunction "2_2") (pintype "passive"))
      (node (ref "U5") (pin "14") (pinfunction "VBAT_14") (pintype "power_in"))
    )
    (net (code "52") (name "VBAT") (class "Default")
      (node (ref "C4") (pin "1") (pinfunction "1_1") (pintype "passive"))
      (node (ref "J2") (pin "1") (pinfunction "1_1") (pintype "passive"))
      (node (ref "Q1") (pin "3") (pinfunction "D_3") (pintype "passive"))
      (node (ref "R1") (pin "7") (pinfunction "2_7") (pintype "passive"))
      (node (ref "U2") (pin "3") (pinfunction "VBAT_3") (pintype "power_in"))
    )
    (net (code "53") (name "VBUS") (class "Default")
      (node (ref "D1") (pin "A") (pinfunction "A_A") (pintype "passive"))
      (node (ref "J1") (pin "1") (pinfunction "VUSB_1") (pintype "passive"))
      (node (ref "Q1") (pin "1") (pinfunction "G_1") (pintype "passive"))
      (node (ref "R1") (pin "8") (pinfunction "2_8") (pintype "passive"))
      (node (ref "R5") (pin "2") (pinfunction "2_2") (pintype "passive"))
      (node (ref "U2") (pin "4") (pinfunction "VDD_4") (pintype "power_in"))
    )
    (net (code "54") (name "VSW") (class "Default")
      (node (ref "U3") (pin "43") (pinfunction "VSW_43") (pintype "power_in"))
    )
    (net (code "55") (name "XIN32") (class "Default")
      (node (ref "C11") (pin "1") (pinfunction "1_1") (pintype "passive"))
      (node (ref "U3") (pin "1") (pinfunction "PA00/EINT0/SERCOM1.0_1") (pintype "bidirectional"))
      (node (ref "X1") (pin "P$2") (pinfunction "P$2_P$2") (pintype "bidirectional"))
    )
    (net (code "56") (name "XOUT32") (class "Default")
      (node (ref "C12") (pin "1") (pinfunction "1_1") (pintype "passive"))
      (node (ref "U3") (pin "2") (pinfunction "PA01/EINT1/SERCOM1.1_2") (pintype "bidirectional"))
      (node (ref "X1") (pin "P$1") (pinfunction "P$1_P$1") (pintype "bidirectional"))
    )
    (net (code "57") (name "unconnected-(NEOPIX-DO-Pad3)") (class "Default")
      (node (ref "NEOPIX") (pin "3") (pinfunction "DO_3") (pintype "output"))
    )
    (net (code "58") (name "unconnected-(R1D-1-Pad4)") (class "Default")
      (node (ref "R1") (pin "4") (pinfunction "1_4") (pintype "passive"))
    )
    (net (code "59") (name "unconnected-(R2C-1-Pad3)") (class "Default")
      (node (ref "R2") (pin "3") (pinfunction "1_3") (pintype "passive"))
    )
    (net (code "60") (name "unconnected-(R2C-2-Pad6)") (class "Default")
      (node (ref "R2") (pin "6") (pinfunction "2_6") (pintype "passive"))
    )
    (net (code "61") (name "unconnected-(S1-Pad1)") (class "Default")
      (node (ref "S1") (pin "1") (pinfunction "1_1") (pintype "passive"))
    )
    (net (code "62") (name "unconnected-(U1-P4-Pad4)") (class "Default")
      (node (ref "U1") (pin "4") (pinfunction "P4_4") (pintype "bidirectional"))
    )
    (net (code "63") (name "unconnected-(U3A-PA22{slash}I2C{slash}16{slash}SERCOM3.0+5.1{slash}I2SDI{slash}PTCX16+Y16-Pad31)") (class "Default")
      (node (ref "U3") (pin "31") (pinfunction "PA22/I2C/16/SERCOM3.0+5.1/I2SDI/PTCX16+Y16_31") (pintype "bidirectional"))
    )
    (net (code "64") (name "unconnected-(U5-32KHZ-Pad1)") (class "Default")
      (node (ref "U5") (pin "1") (pinfunction "32KHZ_1") (pintype "output"))
    )
    (net (code "65") (name "unconnected-(U5-NC-Pad5)") (class "Default")
      (node (ref "U5") (pin "5") (pinfunction "NC_5") (pintype "no_connect"))
    )
    (net (code "66") (name "unconnected-(U5-NC1-Pad6)") (class "Default")
      (node (ref "U5") (pin "6") (pinfunction "NC1_6") (pintype "no_connect"))
    )
    (net (code "67") (name "unconnected-(U5-NC2-Pad7)") (class "Default")
      (node (ref "U5") (pin "7") (pinfunction "NC2_7") (pintype "no_connect"))
    )
    (net (code "68") (name "unconnected-(U5-NC3-Pad8)") (class "Default")
      (node (ref "U5") (pin "8") (pinfunction "NC3_8") (pintype "no_connect"))
    )
    (net (code "69") (name "unconnected-(U5-NC4-Pad9)") (class "Default")
      (node (ref "U5") (pin "9") (pinfunction "NC4_9") (pintype "no_connect"))
    )
    (net (code "70") (name "unconnected-(U5-NC5-Pad10)") (class "Default")
      (node (ref "U5") (pin "10") (pinfunction "NC5_10") (pintype "no_connect"))
    )
    (net (code "71") (name "unconnected-(U5-NC6-Pad11)") (class "Default")
      (node (ref "U5") (pin "11") (pinfunction "NC6_11") (pintype "no_connect"))
    )
    (net (code "72") (name "unconnected-(U5-NC7-Pad12)") (class "Default")
      (node (ref "U5") (pin "12") (pinfunction "NC7_12") (pintype "no_connect"))
    )
    (net (code "73") (name "unconnected-(U5-{slash}RST-Pad4)") (class "Default")
      (node (ref "U5") (pin "4") (pinfunction "/RST_4") (pintype "passive"))
    )
    (net (code "74") (name "~{RESET}") (class "Default")
      (node (ref "R3") (pin "8") (pinfunction "2_8") (pintype "passive"))
      (node (ref "RESET") (pin "P$2") (pinfunction "P$2_P$2") (pintype "passive"))
      (node (ref "TP5") (pin "P$1") (pinfunction "P$1_P$1") (pintype "bidirectional"))
      (node (ref "U3") (pin "40") (pinfunction "RESETN_40") (pintype "passive"))
    )
  )
)
